# 12_TempSensors.net
KiCad netlist of a schematic drawn in Altium Designer
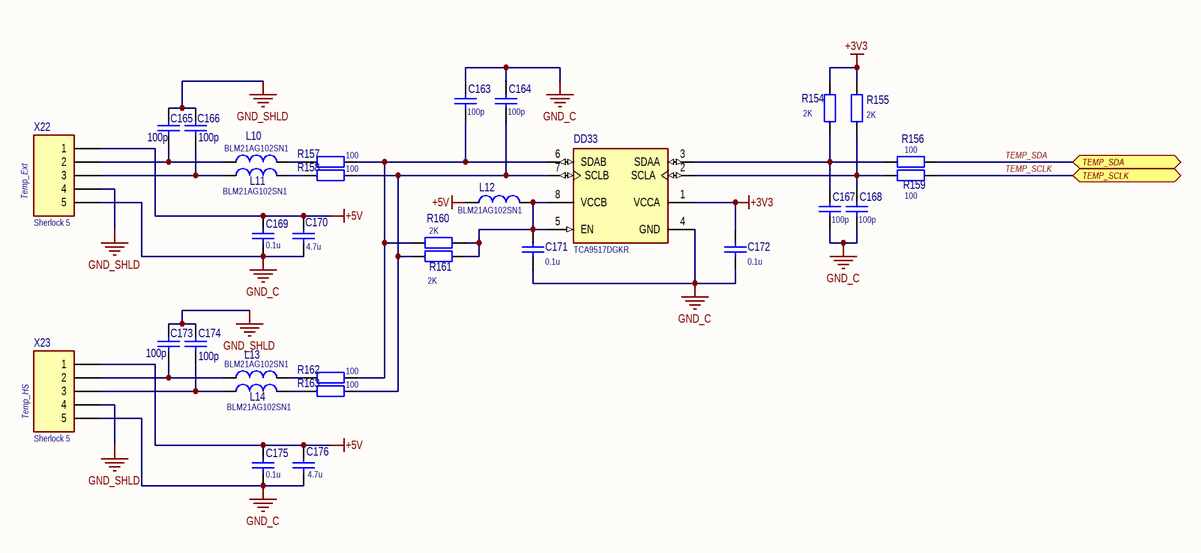
[diagram p0: 12_TempSensors.SchDoc]

(export (version "E")
  (design (tool "Eeschema 10.0.6"))
  (components
    (comp (ref "C163")
      (value "100p")
      (footprint "mainLib:SMD_C_0603")
      (description "SMD C 0603 MURATA 100V 5% NP0")
      (fields (field (name "PARTNUMBER") "GRM1885C2A101JA01") (field (name "MANUFACTURER") "MURATA"))
      (libsource (lib "mainRCLib") (part "C0603 100p 100V 5%"))
    )
    (comp (ref "C164")
      (value "100p")
      (footprint "mainLib:SMD_C_0603")
      (description "SMD C 0603 MURATA 100V 5% NP0")
      (fields (field (name "PARTNUMBER") "GRM1885C2A101JA01") (field (name "MANUFACTURER") "MURATA"))
      (libsource (lib "mainRCLib") (part "C0603 100p 100V 5%"))
    )
    (comp (ref "C165")
      (value "100p")
      (footprint "mainLib:SMD_C_0603")
      (description "SMD C 0603 MURATA 100V 5% NP0")
      (fields (field (name "PARTNUMBER") "GRM1885C2A101JA01") (field (name "MANUFACTURER") "MURATA"))
      (libsource (lib "mainRCLib") (part "C0603 100p 100V 5%"))
    )
    (comp (ref "C166")
      (value "100p")
      (footprint "mainLib:SMD_C_0603")
      (description "SMD C 0603 MURATA 100V 5% NP0")
      (fields (field (name "PARTNUMBER") "GRM1885C2A101JA01") (field (name "MANUFACTURER") "MURATA"))
      (libsource (lib "mainRCLib") (part "C0603 100p 100V 5%"))
    )
    (comp (ref "C167")
      (value "100p")
      (footprint "mainLib:SMD_C_0603")
      (description "SMD C 0603 MURATA 100V 5% NP0")
      (fields (field (name "PARTNUMBER") "GRM1885C2A101JA01") (field (name "MANUFACTURER") "MURATA"))
      (libsource (lib "mainRCLib") (part "C0603 100p 100V 5%"))
    )
    (comp (ref "C168")
      (value "100p")
      (footprint "mainLib:SMD_C_0603")
      (description "SMD C 0603 MURATA 100V 5% NP0")
      (fields (field (name "PARTNUMBER") "GRM1885C2A101JA01") (field (name "MANUFACTURER") "MURATA"))
      (libsource (lib "mainRCLib") (part "C0603 100p 100V 5%"))
    )
    (comp (ref "C169")
      (value "0.1u")
      (footprint "mainLib:SMD_C_0603")
      (description "SMD C 0603 MURATA 50V 10% X7R")
      (fields (field (name "PARTNUMBER") "GRM188R71H104K") (field (name "MANUFACTURER") "MURATA"))
      (libsource (lib "mainRCLib") (part "C0603 0.1u 50V 10%"))
    )
    (comp (ref "C170")
      (value "4.7u")
      (footprint "mainLib:SMD_C_0805")
      (description "SMD C 0805 MURATA 50V 5% NP0")
      (fields (field (name "PARTNUMBER") "GRM21BR61E475M") (field (name "MANUFACTURER") "MURATA"))
      (libsource (lib "mainRCLib") (part "C0805 4.7u 25V 20%  X5R"))
    )
    (comp (ref "C171")
      (value "0.1u")
      (footprint "mainLib:SMD_C_0603")
      (description "SMD C 0603 MURATA 50V 10% X7R")
      (fields (field (name "PARTNUMBER") "GRM188R71H104K") (field (name "MANUFACTURER") "MURATA"))
      (libsource (lib "mainRCLib") (part "C0603 0.1u 50V 10%"))
    )
    (comp (ref "C172")
      (value "0.1u")
      (footprint "mainLib:SMD_C_0603")
      (description "SMD C 0603 MURATA 50V 10% X7R")
      (fields (field (name "PARTNUMBER") "GRM188R71H104K") (field (name "MANUFACTURER") "MURATA"))
      (libsource (lib "mainRCLib") (part "C0603 0.1u 50V 10%"))
    )
    (comp (ref "C173")
      (value "100p")
      (footprint "mainLib:SMD_C_0603")
      (description "SMD C 0603 MURATA 100V 5% NP0")
      (fields (field (name "PARTNUMBER") "GRM1885C2A101JA01") (field (name "MANUFACTURER") "MURATA"))
      (libsource (lib "mainRCLib") (part "C0603 100p 100V 5%"))
    )
    (comp (ref "C174")
      (value "100p")
      (footprint "mainLib:SMD_C_0603")
      (description "SMD C 0603 MURATA 100V 5% NP0")
      (fields (field (name "PARTNUMBER") "GRM1885C2A101JA01") (field (name "MANUFACTURER") "MURATA"))
      (libsource (lib "mainRCLib") (part "C0603 100p 100V 5%"))
    )
    (comp (ref "C175")
      (value "0.1u")
      (footprint "mainLib:SMD_C_0603")
      (description "SMD C 0603 MURATA 50V 10% X7R")
      (fields (field (name "PARTNUMBER") "GRM188R71H104K") (field (name "MANUFACTURER") "MURATA"))
      (libsource (lib "mainRCLib") (part "C0603 0.1u 50V 10%"))
    )
    (comp (ref "C176")
      (value "4.7u")
      (footprint "mainLib:SMD_C_0805")
      (description "SMD C 0805 MURATA 50V 5% NP0")
      (fields (field (name "PARTNUMBER") "GRM21BR61E475M") (field (name "MANUFACTURER") "MURATA"))
      (libsource (lib "mainRCLib") (part "C0805 4.7u 25V 20%  X5R"))
    )
    (comp (ref "DD33")
      (value "TCA9517DGKR")
      (footprint "mainLib:DGK8_M")
      (description "Level-Shifting I 2C Bus Repeater")
      (fields (field (name "MANUFACTURER") "Texas Instruments"))
      (libsource (lib "mainLib") (part "TCA9517DGKR"))
    )
    (comp (ref "L10")
      (value "BLM21AG102SN1")
      (footprint "mainLib:SMD_L_L2_W1.25")
      (description "1000R 0.6A (100MHz)")
      (fields (field (name "MANUFACTURER") "TDK"))
      (libsource (lib "mainLib") (part "BLM21AG102SN1"))
    )
    (comp (ref "L11")
      (value "BLM21AG102SN1")
      (footprint "mainLib:SMD_L_L2_W1.25")
      (description "1000R 0.6A (100MHz)")
      (fields (field (name "MANUFACTURER") "TDK"))
      (libsource (lib "mainLib") (part "BLM21AG102SN1"))
    )
    (comp (ref "L12")
      (value "BLM21AG102SN1")
      (footprint "mainLib:SMD_L_L2_W1.25")
      (description "1000R 0.6A (100MHz)")
      (fields (field (name "MANUFACTURER") "TDK"))
      (libsource (lib "mainLib") (part "BLM21AG102SN1"))
    )
    (comp (ref "L13")
      (value "BLM21AG102SN1")
      (footprint "mainLib:SMD_L_L2_W1.25")
      (description "1000R 0.6A (100MHz)")
      (fields (field (name "MANUFACTURER") "TDK"))
      (libsource (lib "mainLib") (part "BLM21AG102SN1"))
    )
    (comp (ref "L14")
      (value "BLM21AG102SN1")
      (footprint "mainLib:SMD_L_L2_W1.25")
      (description "1000R 0.6A (100MHz)")
      (fields (field (name "MANUFACTURER") "TDK"))
      (libsource (lib "mainLib") (part "BLM21AG102SN1"))
    )
    (comp (ref "R154")
      (value "2K")
      (footprint "mainLib:SMD_R_0603")
      (description "SMD R 0603 VISHAY 0.1W 75V 1% 100ppm")
      (fields (field (name "PARTNUMBER") "CRCW06032K00FK") (field (name "MANUFACTURER") "VISHAY"))
      (libsource (lib "mainRCLib") (part "R0603 2K 1%"))
    )
    (comp (ref "R155")
      (value "2K")
      (footprint "mainLib:SMD_R_0603")
      (description "SMD R 0603 VISHAY 0.1W 75V 1% 100ppm")
      (fields (field (name "PARTNUMBER") "CRCW06032K00FK") (field (name "MANUFACTURER") "VISHAY"))
      (libsource (lib "mainRCLib") (part "R0603 2K 1%"))
    )
    (comp (ref "R156")
      (value "100")
      (footprint "SMD_R_0603")
      (description "SMD R 0603 VISHAY 0.1W 75V 1% 100ppm")
      (fields (field (name "PARTNUMBER") "CRCW0603100RFK") (field (name "MANUFACTURER") "VISHAY"))
      (libsource (lib "mainRCLib") (part "R0603 100 1%"))
    )
    (comp (ref "R157")
      (value "100")
      (footprint "SMD_R_0603")
      (description "SMD R 0603 VISHAY 0.1W 75V 1% 100ppm")
      (fields (field (name "PARTNUMBER") "CRCW0603100RFK") (field (name "MANUFACTURER") "VISHAY"))
      (libsource (lib "mainRCLib") (part "R0603 100 1%"))
    )
    (comp (ref "R158")
      (value "100")
      (footprint "SMD_R_0603")
      (description "SMD R 0603 VISHAY 0.1W 75V 1% 100ppm")
      (fields (field (name "PARTNUMBER") "CRCW0603100RFK") (field (name "MANUFACTURER") "VISHAY"))
      (libsource (lib "mainRCLib") (part "R0603 100 1%"))
    )
    (comp (ref "R159")
      (value "100")
      (footprint "SMD_R_0603")
      (description "SMD R 0603 VISHAY 0.1W 75V 1% 100ppm")
      (fields (field (name "PARTNUMBER") "CRCW0603100RFK") (field (name "MANUFACTURER") "VISHAY"))
      (libsource (lib "mainRCLib") (part "R0603 100 1%"))
    )
    (comp (ref "R160")
      (value "2K")
      (footprint "mainLib:SMD_R_0603")
      (description "SMD R 0603 VISHAY 0.1W 75V 1% 100ppm")
      (fields (field (name "PARTNUMBER") "CRCW06032K00FK") (field (name "MANUFACTURER") "VISHAY"))
      (libsource (lib "") (part "R0603 2K 1%_1"))
    )
    (comp (ref "R161")
      (value "2K")
      (footprint "mainLib:SMD_R_0603")
      (description "SMD R 0603 VISHAY 0.1W 75V 1% 100ppm")
      (fields (field (name "PARTNUMBER") "CRCW06032K00FK") (field (name "MANUFACTURER") "VISHAY"))
      (libsource (lib "") (part "R0603 2K 1%_1"))
    )
    (comp (ref "R162")
      (value "100")
      (footprint "SMD_R_0603")
      (description "SMD R 0603 VISHAY 0.1W 75V 1% 100ppm")
      (fields (field (name "PARTNUMBER") "CRCW0603100RFK") (field (name "MANUFACTURER") "VISHAY"))
      (libsource (lib "mainRCLib") (part "R0603 100 1%"))
    )
    (comp (ref "R163")
      (value "100")
      (footprint "SMD_R_0603")
      (description "SMD R 0603 VISHAY 0.1W 75V 1% 100ppm")
      (fields (field (name "PARTNUMBER") "CRCW0603100RFK") (field (name "MANUFACTURER") "VISHAY"))
      (libsource (lib "mainRCLib") (part "R0603 100 1%"))
    )
    (comp (ref "X22")
      (value "Sherlock 5")
      (footprint "mainLib:35362-0550")
      (description "Sherlock 5 Top, 2A 125V 2mm")
      (fields (field (name "PARTNUMBER") "35362-0550") (field (name "MANUFACTURER") "MOLEX"))
      (libsource (lib "mainLib") (part "35362-0550"))
    )
    (comp (ref "X23")
      (value "Sherlock 5")
      (footprint "mainLib:35362-0550")
      (description "Sherlock 5 Top, 2A 125V 2mm")
      (fields (field (name "PARTNUMBER") "35362-0550") (field (name "MANUFACTURER") "MOLEX"))
      (libsource (lib "mainLib") (part "35362-0550"))
    )
  )
  (nets
    (net (code "1") (name "+3V3") (class "Default")
      (node (ref "C172") (pin "2") (pinfunction "2_2") (pintype "passive"))
      (node (ref "DD33") (pin "1") (pinfunction "VCCA_1") (pintype "power_in"))
      (node (ref "R154") (pin "2") (pinfunction "2_2") (pintype "passive"))
      (node (ref "R155") (pin "2") (pinfunction "2_2") (pintype "passive"))
    )
    (net (code "2") (name "+5V") (class "Default")
      (node (ref "C169") (pin "2") (pinfunction "2_2") (pintype "passive"))
      (node (ref "C170") (pin "2") (pinfunction "2_2") (pintype "passive"))
      (node (ref "C175") (pin "2") (pinfunction "2_2") (pintype "passive"))
      (node (ref "C176") (pin "2") (pinfunction "2_2") (pintype "passive"))
      (node (ref "L12") (pin "1") (pinfunction "1_1") (pintype "passive"))
      (node (ref "X22") (pin "1") (pinfunction "1_1") (pintype "passive"))
      (node (ref "X23") (pin "1") (pinfunction "1_1") (pintype "passive"))
    )
    (net (code "3") (name "/TEMP_SCLK") (class "Default")
      (node (ref "R159") (pin "2") (pinfunction "2_2") (pintype "passive"))
    )
    (net (code "4") (name "/TEMP_SDA") (class "Default")
      (node (ref "R156") (pin "2") (pinfunction "2_2") (pintype "passive"))
    )
    (net (code "5") (name "GND_C") (class "Default")
      (node (ref "C163") (pin "2") (pinfunction "2_2") (pintype "passive"))
      (node (ref "C164") (pin "2") (pinfunction "2_2") (pintype "passive"))
      (node (ref "C167") (pin "1") (pinfunction "1_1") (pintype "passive"))
      (node (ref "C168") (pin "1") (pinfunction "1_1") (pintype "passive"))
      (node (ref "C169") (pin "1") (pinfunction "1_1") (pintype "passive"))
      (node (ref "C170") (pin "1") (pinfunction "1_1") (pintype "passive"))
      (node (ref "C171") (pin "1") (pinfunction "1_1") (pintype "passive"))
      (node (ref "C172") (pin "1") (pinfunction "1_1") (pintype "passive"))
      (node (ref "C175") (pin "1") (pinfunction "1_1") (pintype "passive"))
      (node (ref "C176") (pin "1") (pinfunction "1_1") (pintype "passive"))
      (node (ref "DD33") (pin "4") (pinfunction "GND_4") (pintype "power_in"))
      (node (ref "X22") (pin "5") (pinfunction "5_5") (pintype "passive"))
      (node (ref "X23") (pin "5") (pinfunction "5_5") (pintype "passive"))
    )
    (net (code "6") (name "GND_SHLD") (class "Default")
      (node (ref "C165") (pin "2") (pinfunction "2_2") (pintype "passive"))
      (node (ref "C166") (pin "2") (pinfunction "2_2") (pintype "passive"))
      (node (ref "C173") (pin "2") (pinfunction "2_2") (pintype "passive"))
      (node (ref "C174") (pin "2") (pinfunction "2_2") (pintype "passive"))
      (node (ref "X22") (pin "4") (pinfunction "4_4") (pintype "passive"))
      (node (ref "X23") (pin "4") (pinfunction "4_4") (pintype "passive"))
    )
    (net (code "7") (name "Net-(C165-Pad1)") (class "Default")
      (node (ref "C165") (pin "1") (pinfunction "1_1") (pintype "passive"))
      (node (ref "L10") (pin "1") (pinfunction "1_1") (pintype "passive"))
      (node (ref "X22") (pin "2") (pinfunction "2_2") (pintype "passive"))
    )
    (net (code "8") (name "Net-(C166-Pad1)") (class "Default")
      (node (ref "C166") (pin "1") (pinfunction "1_1") (pintype "passive"))
      (node (ref "L11") (pin "1") (pinfunction "1_1") (pintype "passive"))
      (node (ref "X22") (pin "3") (pinfunction "3_3") (pintype "passive"))
    )
    (net (code "9") (name "Net-(C173-Pad1)") (class "Default")
      (node (ref "C173") (pin "1") (pinfunction "1_1") (pintype "passive"))
      (node (ref "L13") (pin "1") (pinfunction "1_1") (pintype "passive"))
      (node (ref "X23") (pin "2") (pinfunction "2_2") (pintype "passive"))
    )
    (net (code "10") (name "Net-(C174-Pad1)") (class "Default")
      (node (ref "C174") (pin "1") (pinfunction "1_1") (pintype "passive"))
      (node (ref "L14") (pin "1") (pinfunction "1_1") (pintype "passive"))
      (node (ref "X23") (pin "3") (pinfunction "3_3") (pintype "passive"))
    )
    (net (code "11") (name "Net-(DD33-EN)") (class "Default")
      (node (ref "C171") (pin "2") (pinfunction "2_2") (pintype "passive"))
      (node (ref "DD33") (pin "5") (pinfunction "EN_5") (pintype "input"))
      (node (ref "DD33") (pin "8") (pinfunction "VCCB_8") (pintype "power_in"))
      (node (ref "L12") (pin "2") (pinfunction "2_2") (pintype "passive"))
      (node (ref "R160") (pin "2") (pinfunction "2_2") (pintype "passive"))
      (node (ref "R161") (pin "2") (pinfunction "2_2") (pintype "passive"))
    )
    (net (code "12") (name "Net-(DD33-SCLA)") (class "Default")
      (node (ref "C168") (pin "2") (pinfunction "2_2") (pintype "passive"))
      (node (ref "DD33") (pin "2") (pinfunction "SCLA_2") (pintype "bidirectional"))
      (node (ref "R155") (pin "1") (pinfunction "1_1") (pintype "passive"))
      (node (ref "R159") (pin "1") (pinfunction "1_1") (pintype "passive"))
    )
    (net (code "13") (name "Net-(DD33-SCLB)") (class "Default")
      (node (ref "C164") (pin "1") (pinfunction "1_1") (pintype "passive"))
      (node (ref "DD33") (pin "7") (pinfunction "SCLB_7") (pintype "bidirectional"))
      (node (ref "R158") (pin "2") (pinfunction "2_2") (pintype "passive"))
      (node (ref "R161") (pin "1") (pinfunction "1_1") (pintype "passive"))
      (node (ref "R163") (pin "2") (pinfunction "2_2") (pintype "passive"))
    )
    (net (code "14") (name "Net-(DD33-SDAA)") (class "Default")
      (node (ref "C167") (pin "2") (pinfunction "2_2") (pintype "passive"))
      (node (ref "DD33") (pin "3") (pinfunction "SDAA_3") (pintype "bidirectional"))
      (node (ref "R154") (pin "1") (pinfunction "1_1") (pintype "passive"))
      (node (ref "R156") (pin "1") (pinfunction "1_1") (pintype "passive"))
    )
    (net (code "15") (name "Net-(DD33-SDAB)") (class "Default")
      (node (ref "C163") (pin "1") (pinfunction "1_1") (pintype "passive"))
      (node (ref "DD33") (pin "6") (pinfunction "SDAB_6") (pintype "bidirectional"))
      (node (ref "R157") (pin "2") (pinfunction "2_2") (pintype "passive"))
      (node (ref "R160") (pin "1") (pinfunction "1_1") (pintype "passive"))
      (node (ref "R162") (pin "2") (pinfunction "2_2") (pintype "passive"))
    )
    (net (code "16") (name "Net-(L10-Pad2)") (class "Default")
      (node (ref "L10") (pin "2") (pinfunction "2_2") (pintype "passive"))
      (node (ref "R157") (pin "1") (pinfunction "1_1") (pintype "passive"))
    )
    (net (code "17") (name "Net-(L11-Pad2)") (class "Default")
      (node (ref "L11") (pin "2") (pinfunction "2_2") (pintype "passive"))
      (node (ref "R158") (pin "1") (pinfunction "1_1") (pintype "passive"))
    )
    (net (code "18") (name "Net-(L13-Pad2)") (class "Default")
      (node (ref "L13") (pin "2") (pinfunction "2_2") (pintype "passive"))
      (node (ref "R162") (pin "1") (pinfunction "1_1") (pintype "passive"))
    )
    (net (code "19") (name "Net-(L14-Pad2)") (class "Default")
      (node (ref "L14") (pin "2") (pinfunction "2_2") (pintype "passive"))
      (node (ref "R163") (pin "1") (pinfunction "1_1") (pintype "passive"))
    )
  )
)
